# 02_IO_Interface.net
KiCad netlist of a schematic drawn in Altium Designer
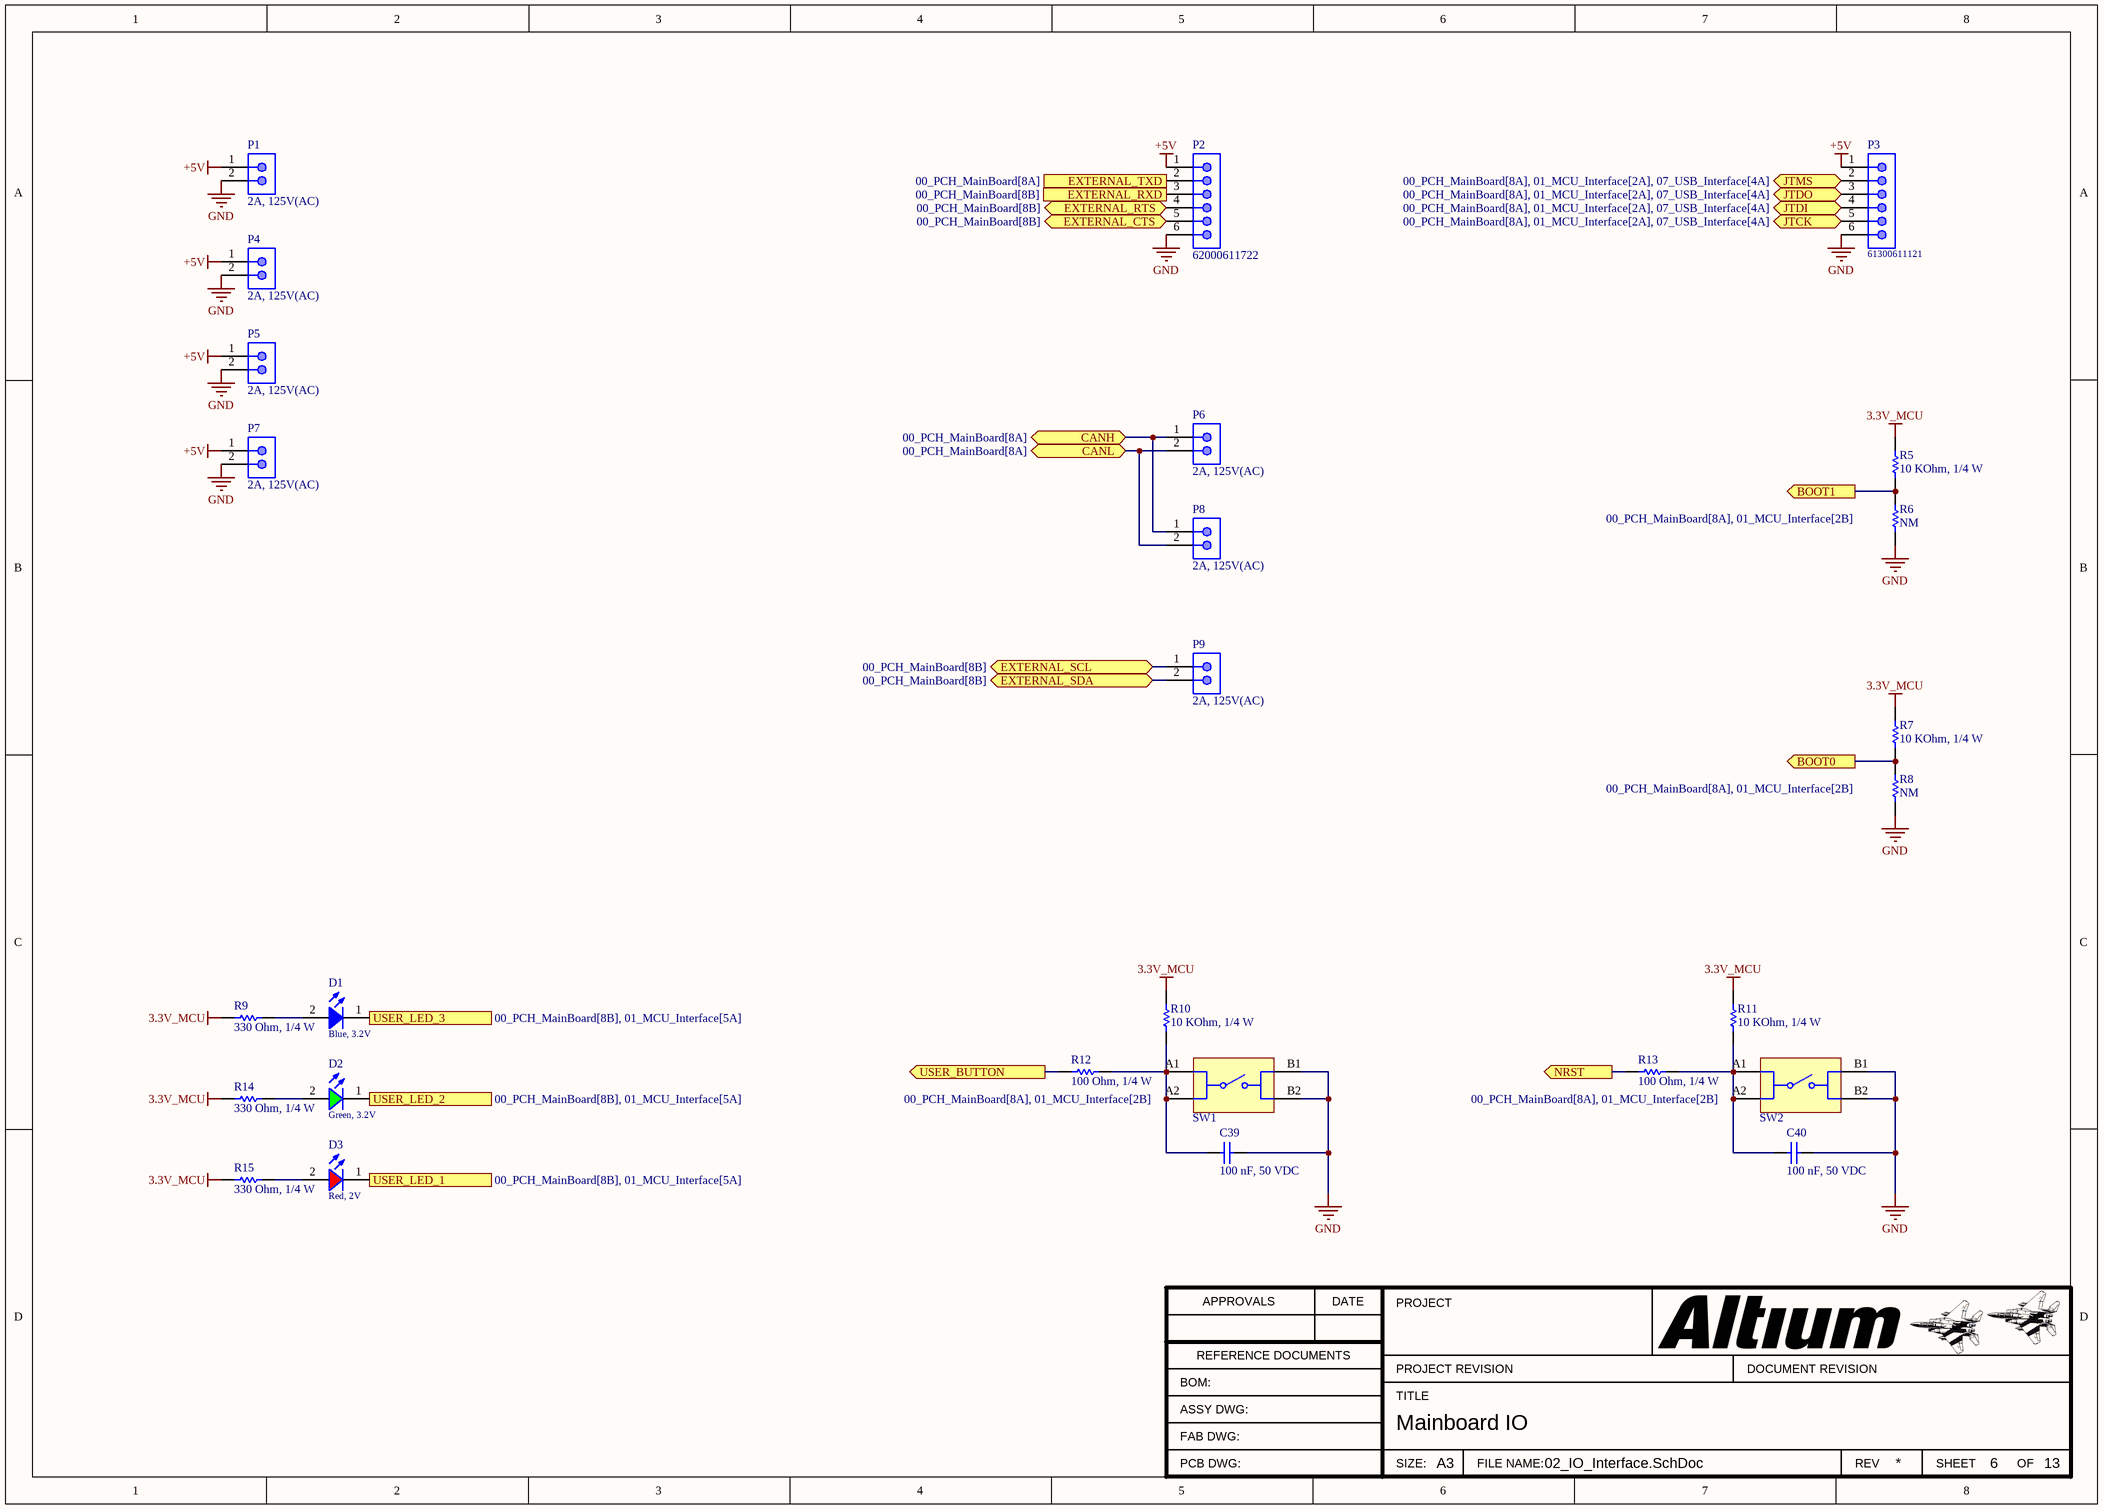
[diagram p0: 02_IO_Interface.SchDoc]

(export (version "E")
  (design (tool "Eeschema 10.0.6"))
  (components
    (comp (ref "C39")
      (value "100 nF, 50 VDC")
      (footprint "CAP_0603")
      (description "CAP, size 0603, 100 nF, 50 VDC")
      (fields (field (name "TOLERANCE") "+/-10%"))
      (libsource (lib "Altium_Ceramic_Cap") (part "0106031041050"))
    )
    (comp (ref "C40")
      (value "100 nF, 50 VDC")
      (footprint "CAP_0603")
      (description "CAP, size 0603, 100 nF, 50 VDC")
      (fields (field (name "TOLERANCE") "+/-10%"))
      (libsource (lib "Altium_Ceramic_Cap") (part "0106031041050"))
    )
    (comp (ref "D1")
      (value "Blue, 3.2V")
      (footprint "WL-SMCW_0603_H=0.7mm")
      (description "WL-SMCW SMT Mono-color Chip LED Blur, size 0603, Blue, 3.2V, 140deg")
      (libsource (lib "Altium_LED") (part "160603BlueBlur"))
    )
    (comp (ref "D2")
      (value "Green, 3.2V")
      (footprint "WL-SMCW_0603_H=0.7mm")
      (description "WL-SMCW SMT Mono-color Chip LED Blur, size 0603, Green, 3.2V, 140deg")
      (libsource (lib "Altium_LED") (part "160603GreenBlur"))
    )
    (comp (ref "D3")
      (value "Red, 2V")
      (footprint "WL-SMCW_0603_H=0.7mm")
      (description "WL-SMCW SMT Mono-color Chip LED Blur, size 0603, Red, 2V, 140deg")
      (libsource (lib "Altium_LED") (part "160603RedBlur"))
    )
    (comp (ref "P1")
      (value "2A, 125V(AC)")
      (footprint "620102131822")
      (description "WR-WTB SMT Male Horizontal Shrouded Header, pitch 2mm, 2p")
      (fields (field (name "PART NUMBER") "620102131822") (field (name "PUBLISHER") "Wurth Elektronik"))
      (libsource (lib "Altium_PCB_Connector") (part "620102131822"))
    )
    (comp (ref "P2")
      (value "62000611722")
      (footprint "62000611722")
      (description "WR-WTB THT Male Horizontal Shrouded Header, pitch 2mm, 6p")
      (fields (field (name "PUBLISHER") "Wurth Elektronik"))
      (libsource (lib "Altium_PCB_Connector") (part "62000611722"))
    )
    (comp (ref "P3")
      (value "61300611121")
      (footprint "61300611121")
      (description "WR-PHD Pin Header, THT, pitch 2.54mm, Single Row, Vertical, 6p")
      (fields (field (name "MANUFACTURER") "Wurth Elektronik"))
      (libsource (lib "Altium_Header") (part "61300611121"))
    )
    (comp (ref "P4")
      (value "2A, 125V(AC)")
      (footprint "620102131822")
      (description "WR-WTB SMT Male Horizontal Shrouded Header, pitch 2mm, 2p")
      (fields (field (name "PART NUMBER") "620102131822") (field (name "PUBLISHER") "Wurth Elektronik"))
      (libsource (lib "Altium_PCB_Connector") (part "620102131822"))
    )
    (comp (ref "P5")
      (value "2A, 125V(AC)")
      (footprint "620102131822")
      (description "WR-WTB SMT Male Horizontal Shrouded Header, pitch 2mm, 2p")
      (fields (field (name "PART NUMBER") "620102131822") (field (name "PUBLISHER") "Wurth Elektronik"))
      (libsource (lib "Altium_PCB_Connector") (part "620102131822"))
    )
    (comp (ref "P6")
      (value "2A, 125V(AC)")
      (footprint "620102131822")
      (description "WR-WTB SMT Male Horizontal Shrouded Header, pitch 2mm, 2p")
      (fields (field (name "PART NUMBER") "620102131822") (field (name "PUBLISHER") "Wurth Elektronik"))
      (libsource (lib "Altium_PCB_Connector") (part "620102131822"))
    )
    (comp (ref "P7")
      (value "2A, 125V(AC)")
      (footprint "620102131822")
      (description "WR-WTB SMT Male Horizontal Shrouded Header, pitch 2mm, 2p")
      (fields (field (name "PART NUMBER") "620102131822") (field (name "PUBLISHER") "Wurth Elektronik"))
      (libsource (lib "Altium_PCB_Connector") (part "620102131822"))
    )
    (comp (ref "P8")
      (value "2A, 125V(AC)")
      (footprint "620102131822")
      (description "WR-WTB SMT Male Horizontal Shrouded Header, pitch 2mm, 2p")
      (fields (field (name "PART NUMBER") "620102131822") (field (name "PUBLISHER") "Wurth Elektronik"))
      (libsource (lib "Altium_PCB_Connector") (part "620102131822"))
    )
    (comp (ref "P9")
      (value "2A, 125V(AC)")
      (footprint "620102131822")
      (description "WR-WTB SMT Male Horizontal Shrouded Header, pitch 2mm, 2p")
      (fields (field (name "PART NUMBER") "620102131822") (field (name "PUBLISHER") "Wurth Elektronik"))
      (libsource (lib "Altium_PCB_Connector") (part "620102131822"))
    )
    (comp (ref "R5")
      (value "10 KOhm, 1/4 W")
      (footprint "resistor_0603")
      (description "RES, size 0603, 10 KOhm, 1/4 W")
      (libsource (lib "Altium_Resistor") (part "0006031031"))
    )
    (comp (ref "R6")
      (value "NM")
      (footprint "resistor_0603")
      (description "RES, size 0603, NM")
      (libsource (lib "Altium_Resistor") (part "000603_NM"))
    )
    (comp (ref "R7")
      (value "10 KOhm, 1/4 W")
      (footprint "resistor_0603")
      (description "RES, size 0603, 10 KOhm, 1/4 W")
      (libsource (lib "Altium_Resistor") (part "0006031031"))
    )
    (comp (ref "R8")
      (value "NM")
      (footprint "resistor_0603")
      (description "RES, size 0603, NM")
      (libsource (lib "Altium_Resistor") (part "000603_NM"))
    )
    (comp (ref "R9")
      (value "330 Ohm, 1/4 W")
      (footprint "resistor_0603")
      (description "RES, size 0603, 330 Ohm, 1/4 W")
      (libsource (lib "Altium_Resistor") (part "0006033311"))
    )
    (comp (ref "R10")
      (value "10 KOhm, 1/4 W")
      (footprint "resistor_0603")
      (description "RES, size 0603, 10 KOhm, 1/4 W")
      (libsource (lib "Altium_Resistor") (part "0006031031"))
    )
    (comp (ref "R11")
      (value "10 KOhm, 1/4 W")
      (footprint "resistor_0603")
      (description "RES, size 0603, 10 KOhm, 1/4 W")
      (libsource (lib "Altium_Resistor") (part "0006031031"))
    )
    (comp (ref "R12")
      (value "100 Ohm, 1/4 W")
      (footprint "resistor_0603")
      (description "RES, size 0603, 100 Ohm, 1/4 W")
      (libsource (lib "Altium_Resistor") (part "0006031011"))
    )
    (comp (ref "R13")
      (value "100 Ohm, 1/4 W")
      (footprint "resistor_0603")
      (description "RES, size 0603, 100 Ohm, 1/4 W")
      (libsource (lib "Altium_Resistor") (part "0006031011"))
    )
    (comp (ref "R14")
      (value "330 Ohm, 1/4 W")
      (footprint "resistor_0603")
      (description "RES, size 0603, 330 Ohm, 1/4 W")
      (libsource (lib "Altium_Resistor") (part "0006033311"))
    )
    (comp (ref "R15")
      (value "330 Ohm, 1/4 W")
      (footprint "resistor_0603")
      (description "RES, size 0603, 330 Ohm, 1/4 W")
      (libsource (lib "Altium_Resistor") (part "0006033311"))
    )
    (comp (ref "SW1")
      (value "430451035836")
      (footprint "WS-TASV_L6W6H3.5_4304x10358x6")
      (description "WS-TASV SMT Washable Tact Switch, L6 x W6 x H3.5mm, 360g, SPST-NO, 12V, 50mA")
      (fields (field (name "MANUFACTURER") "Wurth Elektronik"))
      (libsource (lib "Altium_Button") (part "430451035836"))
    )
    (comp (ref "SW2")
      (value "430451035836")
      (footprint "WS-TASV_L6W6H3.5_4304x10358x6")
      (description "WS-TASV SMT Washable Tact Switch, L6 x W6 x H3.5mm, 360g, SPST-NO, 12V, 50mA")
      (fields (field (name "MANUFACTURER") "Wurth Elektronik"))
      (libsource (lib "Altium_Button") (part "430451035836"))
    )
  )
  (nets
    (net (code "1") (name "+5V") (class "Default")
      (node (ref "P1") (pin "1") (pinfunction "1_1") (pintype "passive"))
      (node (ref "P2") (pin "1") (pinfunction "1_1") (pintype "passive"))
      (node (ref "P3") (pin "1") (pinfunction "1_1") (pintype "passive"))
      (node (ref "P4") (pin "1") (pinfunction "1_1") (pintype "passive"))
      (node (ref "P5") (pin "1") (pinfunction "1_1") (pintype "passive"))
      (node (ref "P7") (pin "1") (pinfunction "1_1") (pintype "passive"))
    )
    (net (code "2") (name "/BOOT0") (class "Default")
      (node (ref "R7") (pin "1") (pinfunction "1_1") (pintype "passive"))
      (node (ref "R8") (pin "2") (pinfunction "2_2") (pintype "passive"))
    )
    (net (code "3") (name "/BOOT1") (class "Default")
      (node (ref "R5") (pin "1") (pinfunction "1_1") (pintype "passive"))
      (node (ref "R6") (pin "2") (pinfunction "2_2") (pintype "passive"))
    )
    (net (code "4") (name "/CANH") (class "Default")
      (node (ref "P6") (pin "1") (pinfunction "1_1") (pintype "passive"))
      (node (ref "P8") (pin "1") (pinfunction "1_1") (pintype "passive"))
    )
    (net (code "5") (name "/CANL") (class "Default")
      (node (ref "P6") (pin "2") (pinfunction "2_2") (pintype "passive"))
      (node (ref "P8") (pin "2") (pinfunction "2_2") (pintype "passive"))
    )
    (net (code "6") (name "/EXTERNAL_CTS") (class "Default")
      (node (ref "P2") (pin "5") (pinfunction "5_5") (pintype "passive"))
    )
    (net (code "7") (name "/EXTERNAL_RTS") (class "Default")
      (node (ref "P2") (pin "4") (pinfunction "4_4") (pintype "passive"))
    )
    (net (code "8") (name "/EXTERNAL_RXD") (class "Default")
      (node (ref "P2") (pin "3") (pinfunction "3_3") (pintype "passive"))
    )
    (net (code "9") (name "/EXTERNAL_SCL") (class "Default")
      (node (ref "P9") (pin "1") (pinfunction "1_1") (pintype "passive"))
    )
    (net (code "10") (name "/EXTERNAL_SDA") (class "Default")
      (node (ref "P9") (pin "2") (pinfunction "2_2") (pintype "passive"))
    )
    (net (code "11") (name "/EXTERNAL_TXD") (class "Default")
      (node (ref "P2") (pin "2") (pinfunction "2_2") (pintype "passive"))
    )
    (net (code "12") (name "/JTCK") (class "Default")
      (node (ref "P3") (pin "5") (pinfunction "5_5") (pintype "passive"))
    )
    (net (code "13") (name "/JTDI") (class "Default")
      (node (ref "P3") (pin "4") (pinfunction "4_4") (pintype "passive"))
    )
    (net (code "14") (name "/JTDO") (class "Default")
      (node (ref "P3") (pin "3") (pinfunction "3_3") (pintype "passive"))
    )
    (net (code "15") (name "/JTMS") (class "Default")
      (node (ref "P3") (pin "2") (pinfunction "2_2") (pintype "passive"))
    )
    (net (code "16") (name "/NRST") (class "Default")
      (node (ref "R13") (pin "1") (pinfunction "1_1") (pintype "passive"))
    )
    (net (code "17") (name "/USER_BUTTON") (class "Default")
      (node (ref "R12") (pin "1") (pinfunction "1_1") (pintype "passive"))
    )
    (net (code "18") (name "/USER_LED_1") (class "Default")
      (node (ref "D3") (pin "1") (pinfunction "K_1") (pintype "passive"))
    )
    (net (code "19") (name "/USER_LED_2") (class "Default")
      (node (ref "D2") (pin "1") (pinfunction "K_1") (pintype "passive"))
    )
    (net (code "20") (name "/USER_LED_3") (class "Default")
      (node (ref "D1") (pin "1") (pinfunction "K_1") (pintype "passive"))
    )
    (net (code "21") (name "3.3V_MCU") (class "Default")
      (node (ref "R10") (pin "2") (pinfunction "2_2") (pintype "passive"))
      (node (ref "R11") (pin "2") (pinfunction "2_2") (pintype "passive"))
      (node (ref "R14") (pin "2") (pinfunction "2_2") (pintype "passive"))
      (node (ref "R15") (pin "2") (pinfunction "2_2") (pintype "passive"))
      (node (ref "R5") (pin "2") (pinfunction "2_2") (pintype "passive"))
      (node (ref "R7") (pin "2") (pinfunction "2_2") (pintype "passive"))
      (node (ref "R9") (pin "2") (pinfunction "2_2") (pintype "passive"))
    )
    (net (code "22") (name "GND") (class "Default")
      (node (ref "C39") (pin "2") (pinfunction "2_2") (pintype "passive"))
      (node (ref "C40") (pin "2") (pinfunction "2_2") (pintype "passive"))
      (node (ref "P1") (pin "2") (pinfunction "2_2") (pintype "passive"))
      (node (ref "P2") (pin "6") (pinfunction "6_6") (pintype "passive"))
      (node (ref "P3") (pin "6") (pinfunction "6_6") (pintype "passive"))
      (node (ref "P4") (pin "2") (pinfunction "2_2") (pintype "passive"))
      (node (ref "P5") (pin "2") (pinfunction "2_2") (pintype "passive"))
      (node (ref "P7") (pin "2") (pinfunction "2_2") (pintype "passive"))
      (node (ref "R6") (pin "1") (pinfunction "1_1") (pintype "passive"))
      (node (ref "R8") (pin "1") (pinfunction "1_1") (pintype "passive"))
      (node (ref "SW1") (pin "B1") (pinfunction "B1_B1") (pintype "passive"))
      (node (ref "SW1") (pin "B2") (pinfunction "B2_B2") (pintype "passive"))
      (node (ref "SW2") (pin "B1") (pinfunction "B1_B1") (pintype "passive"))
      (node (ref "SW2") (pin "B2") (pinfunction "B2_B2") (pintype "passive"))
    )
    (net (code "23") (name "Net-(C39-Pad1)") (class "Default")
      (node (ref "C39") (pin "1") (pinfunction "1_1") (pintype "passive"))
      (node (ref "R10") (pin "1") (pinfunction "1_1") (pintype "passive"))
      (node (ref "R12") (pin "2") (pinfunction "2_2") (pintype "passive"))
      (node (ref "SW1") (pin "A1") (pinfunction "A1_A1") (pintype "passive"))
      (node (ref "SW1") (pin "A2") (pinfunction "A2_A2") (pintype "passive"))
    )
    (net (code "24") (name "Net-(C40-Pad1)") (class "Default")
      (node (ref "C40") (pin "1") (pinfunction "1_1") (pintype "passive"))
      (node (ref "R11") (pin "1") (pinfunction "1_1") (pintype "passive"))
      (node (ref "R13") (pin "2") (pinfunction "2_2") (pintype "passive"))
      (node (ref "SW2") (pin "A1") (pinfunction "A1_A1") (pintype "passive"))
      (node (ref "SW2") (pin "A2") (pinfunction "A2_A2") (pintype "passive"))
    )
    (net (code "25") (name "Net-(D1-A)") (class "Default")
      (node (ref "D1") (pin "2") (pinfunction "A_2") (pintype "passive"))
      (node (ref "R9") (pin "1") (pinfunction "1_1") (pintype "passive"))
    )
    (net (code "26") (name "Net-(D2-A)") (class "Default")
      (node (ref "D2") (pin "2") (pinfunction "A_2") (pintype "passive"))
      (node (ref "R14") (pin "1") (pinfunction "1_1") (pintype "passive"))
    )
    (net (code "27") (name "Net-(D3-A)") (class "Default")
      (node (ref "D3") (pin "2") (pinfunction "A_2") (pintype "passive"))
      (node (ref "R15") (pin "1") (pinfunction "1_1") (pintype "passive"))
    )
  )
)
